# RapideUSB.net
KiCad netlist of a schematic drawn in EAGLE
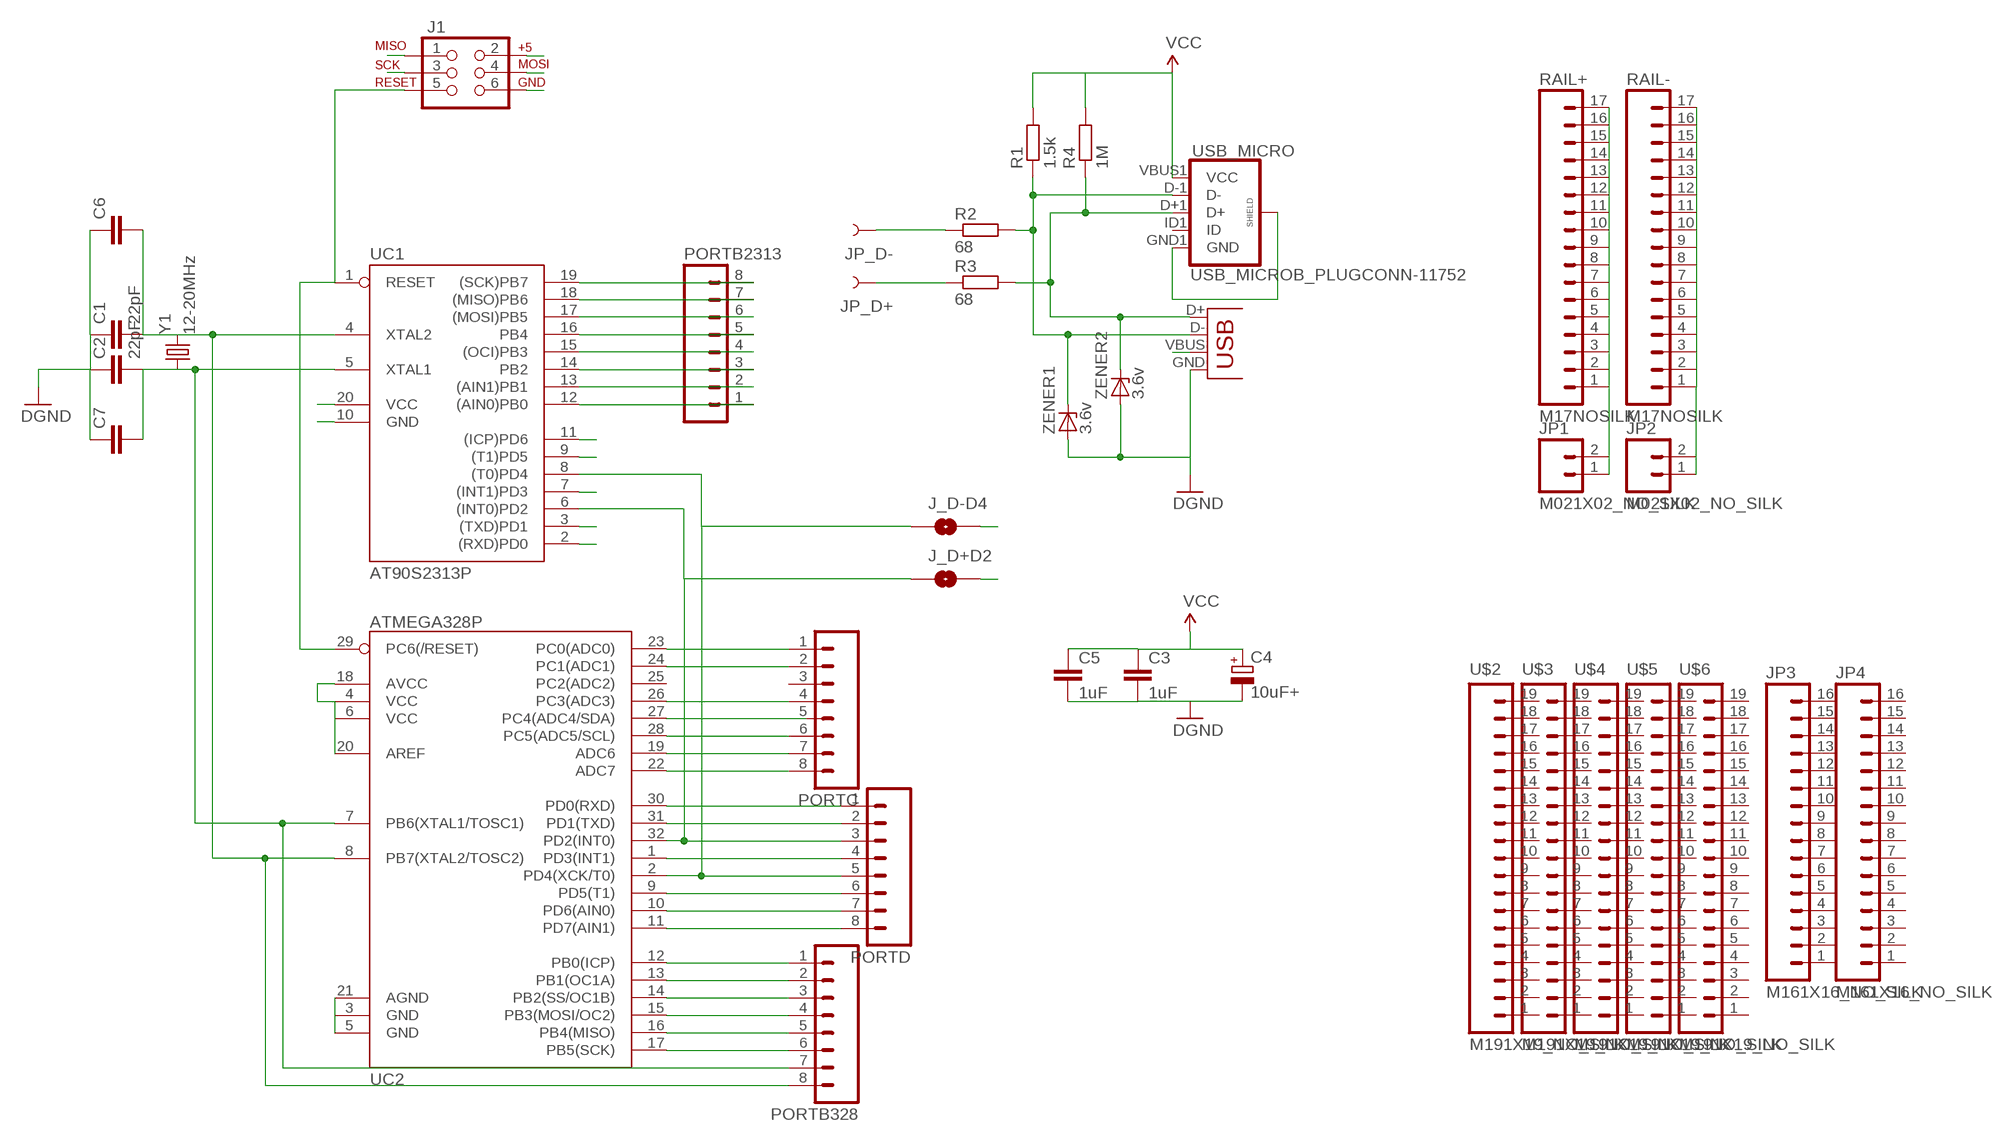
[diagram p0: schematic, sheet 1]

(export (version "E")
  (design (tool "Eeschema 10.0.6"))
  (components
    (comp (ref "C1")
      (value "22pF")
      (footprint "eagle-import:C025-024X044")
      (libsource (lib "eagle-import") (part "C-EU025-024X044"))
    )
    (comp (ref "C2")
      (value "22pF")
      (footprint "eagle-import:C025-024X044")
      (libsource (lib "eagle-import") (part "C-EU025-024X044"))
    )
    (comp (ref "C3")
      (value "1uF")
      (footprint "eagle-import:C025-024X044")
      (libsource (lib "eagle-import") (part "C-EU025-024X044"))
    )
    (comp (ref "C4")
      (value "10uF+")
      (footprint "eagle-import:E2-5")
      (libsource (lib "eagle-import") (part "CPOL-EUE2-5"))
    )
    (comp (ref "C5")
      (value "1uF")
      (footprint "eagle-import:C025-024X044")
      (libsource (lib "eagle-import") (part "C-EU025-024X044"))
    )
    (comp (ref "C6")
      (value "C-EUC1206K")
      (footprint "eagle-import:C1206K")
      (libsource (lib "eagle-import") (part "C-EUC1206K"))
    )
    (comp (ref "C7")
      (value "C-EUC1206K")
      (footprint "eagle-import:C1206K")
      (libsource (lib "eagle-import") (part "C-EUC1206K"))
    )
    (comp (ref "J1")
      (value "AVR_SPI_PRG_6PTH")
      (footprint "eagle-import:2X3")
      (libsource (lib "eagle-import") (part "AVR_SPI_PRG_6PTH"))
    )
    (comp (ref "JP1")
      (value "M021X02_NO_SILK")
      (footprint "eagle-import:1X02_NO_SILK")
      (libsource (lib "eagle-import") (part "M021X02_NO_SILK"))
    )
    (comp (ref "JP2")
      (value "M021X02_NO_SILK")
      (footprint "eagle-import:1X02_NO_SILK")
      (libsource (lib "eagle-import") (part "M021X02_NO_SILK"))
    )
    (comp (ref "JP3")
      (value "M161X16_NO_SILK")
      (footprint "eagle-import:1X16_NO_SILK")
      (libsource (lib "eagle-import") (part "M161X16_NO_SILK"))
    )
    (comp (ref "JP4")
      (value "M161X16_NO_SILK")
      (footprint "eagle-import:1X16_NO_SILK")
      (libsource (lib "eagle-import") (part "M161X16_NO_SILK"))
    )
    (comp (ref "JP_D+")
      (value "TEST-POINT3X5")
      (footprint "eagle-import:PAD.03X.05")
      (libsource (lib "eagle-import") (part "TEST-POINT3X5"))
    )
    (comp (ref "JP_D-")
      (value "TEST-POINT3X5")
      (footprint "eagle-import:PAD.03X.05")
      (libsource (lib "eagle-import") (part "TEST-POINT3X5"))
    )
    (comp (ref "J_D+D2")
      (value "JUMPER-PAD-2-NOYES_SILK")
      (footprint "eagle-import:PAD-JUMPER-2-NO_YES_SILK")
      (libsource (lib "eagle-import") (part "JUMPER-PAD-2-NOYES_SILK"))
    )
    (comp (ref "J_D-D4")
      (value "JUMPER-PAD-2-NOYES_SILK")
      (footprint "eagle-import:PAD-JUMPER-2-NO_YES_SILK")
      (libsource (lib "eagle-import") (part "JUMPER-PAD-2-NOYES_SILK"))
    )
    (comp (ref "PORTB328")
      (value "M081X08")
      (footprint "eagle-import:1X08")
      (libsource (lib "eagle-import") (part "M081X08"))
    )
    (comp (ref "PORTB2313")
      (value "M081X08")
      (footprint "eagle-import:1X08")
      (libsource (lib "eagle-import") (part "M081X08"))
    )
    (comp (ref "PORTC")
      (value "M081X08")
      (footprint "eagle-import:1X08")
      (libsource (lib "eagle-import") (part "M081X08"))
    )
    (comp (ref "PORTD")
      (value "M081X08")
      (footprint "eagle-import:1X08")
      (libsource (lib "eagle-import") (part "M081X08"))
    )
    (comp (ref "R1")
      (value "1.5k")
      (footprint "eagle-import:0204V")
      (libsource (lib "eagle-import") (part "R-EU_0204/2V"))
    )
    (comp (ref "R2")
      (value "68")
      (footprint "eagle-import:0204V")
      (libsource (lib "eagle-import") (part "R-EU_0204/2V"))
    )
    (comp (ref "R3")
      (value "68")
      (footprint "eagle-import:0204V")
      (libsource (lib "eagle-import") (part "R-EU_0204/2V"))
    )
    (comp (ref "R4")
      (value "1M")
      (footprint "eagle-import:0204V")
      (libsource (lib "eagle-import") (part "R-EU_0204/2V"))
    )
    (comp (ref "RAIL+")
      (value "M17NOSILK")
      (footprint "eagle-import:1X17_NO_SILK")
      (libsource (lib "eagle-import") (part "M17NOSILK"))
    )
    (comp (ref "RAIL-")
      (value "M17NOSILK")
      (footprint "eagle-import:1X17_NO_SILK")
      (libsource (lib "eagle-import") (part "M17NOSILK"))
    )
    (comp (ref "U$2")
      (value "M191X19_NO_SILK")
      (footprint "eagle-import:1X19_NO_SILK")
      (libsource (lib "eagle-import") (part "M191X19_NO_SILK"))
    )
    (comp (ref "U$3")
      (value "M191X19_NO_SILK")
      (footprint "eagle-import:1X19_NO_SILK")
      (libsource (lib "eagle-import") (part "M191X19_NO_SILK"))
    )
    (comp (ref "U$4")
      (value "M191X19_NO_SILK")
      (footprint "eagle-import:1X19_NO_SILK")
      (libsource (lib "eagle-import") (part "M191X19_NO_SILK"))
    )
    (comp (ref "U$5")
      (value "M191X19_NO_SILK")
      (footprint "eagle-import:1X19_NO_SILK")
      (libsource (lib "eagle-import") (part "M191X19_NO_SILK"))
    )
    (comp (ref "U$6")
      (value "M191X19_NO_SILK")
      (footprint "eagle-import:1X19_NO_SILK")
      (libsource (lib "eagle-import") (part "M191X19_NO_SILK"))
    )
    (comp (ref "UC1")
      (value "AT90S2313P")
      (footprint "eagle-import:DIL20")
      (libsource (lib "eagle-import") (part "AT90S2313P"))
    )
    (comp (ref "UC2")
      (value "ATMEGA328P")
      (footprint "eagle-import:TQFP32-08")
      (libsource (lib "eagle-import") (part "ATMEGA328_SMT"))
    )
    (comp (ref "USB_MICRO")
      (value "USB_MICROB_PLUGCONN-11752")
      (footprint "eagle-import:USB-B-MICRO-SMD_V03")
      (libsource (lib "eagle-import") (part "USB_MICROB_PLUGCONN-11752"))
    )
    (comp (ref "USB_MINI")
      (value "USBSMD")
      (footprint "eagle-import:USB-MINIB")
      (libsource (lib "eagle-import") (part "USBSMD"))
    )
    (comp (ref "Y1")
      (value "12-20MHz")
      (footprint "eagle-import:HC49U-V")
      (libsource (lib "eagle-import") (part "CRYSTALHC49UV"))
    )
    (comp (ref "ZENER1")
      (value "3.6v")
      (footprint "eagle-import:ZDIO-2.5")
      (libsource (lib "eagle-import") (part "ZENER-DIODEZD-2.5"))
    )
    (comp (ref "ZENER2")
      (value "3.6v")
      (footprint "eagle-import:ZDIO-2.5")
      (libsource (lib "eagle-import") (part "ZENER-DIODEZD-2.5"))
    )
  )
  (nets
    (net (code "1") (name "/D+") (class "Default")
      (node (ref "JP_D+") (pin "P$1") (pinfunction "1_P$1") (pintype "bidirectional"))
      (node (ref "J_D+D2") (pin "2") (pinfunction "2_2") (pintype "passive"))
      (node (ref "R3") (pin "1") (pinfunction "1_1") (pintype "passive"))
    )
    (net (code "2") (name "/D-") (class "Default")
      (node (ref "JP_D-") (pin "P$1") (pinfunction "1_P$1") (pintype "bidirectional"))
      (node (ref "J_D-D4") (pin "2") (pinfunction "2_2") (pintype "passive"))
      (node (ref "R2") (pin "1") (pinfunction "1_1") (pintype "passive"))
    )
    (net (code "3") (name "/D0") (class "Default")
      (node (ref "PORTD") (pin "1") (pinfunction "1_1") (pintype "passive"))
      (node (ref "UC1") (pin "2") (pinfunction "(RXD)PD0_2") (pintype "bidirectional"))
      (node (ref "UC2") (pin "30") (pinfunction "PD0(RXD)_30") (pintype "bidirectional"))
    )
    (net (code "4") (name "/D1") (class "Default")
      (node (ref "PORTD") (pin "2") (pinfunction "2_2") (pintype "passive"))
      (node (ref "UC1") (pin "3") (pinfunction "(TXD)PD1_3") (pintype "bidirectional"))
      (node (ref "UC2") (pin "31") (pinfunction "PD1(TXD)_31") (pintype "bidirectional"))
    )
    (net (code "5") (name "/D3") (class "Default")
      (node (ref "PORTD") (pin "4") (pinfunction "4_4") (pintype "passive"))
      (node (ref "UC1") (pin "7") (pinfunction "(INT1)PD3_7") (pintype "bidirectional"))
      (node (ref "UC2") (pin "1") (pinfunction "PD3(INT1)_1") (pintype "bidirectional"))
    )
    (net (code "6") (name "/D5") (class "Default")
      (node (ref "PORTD") (pin "6") (pinfunction "6_6") (pintype "passive"))
      (node (ref "UC1") (pin "9") (pinfunction "(T1)PD5_9") (pintype "bidirectional"))
      (node (ref "UC2") (pin "9") (pinfunction "PD5(T1)_9") (pintype "bidirectional"))
    )
    (net (code "7") (name "/D6") (class "Default")
      (node (ref "PORTD") (pin "7") (pinfunction "7_7") (pintype "passive"))
      (node (ref "UC1") (pin "11") (pinfunction "(ICP)PD6_11") (pintype "bidirectional"))
      (node (ref "UC2") (pin "10") (pinfunction "PD6(AIN0)_10") (pintype "bidirectional"))
    )
    (net (code "8") (name "/MISO") (class "Default")
      (node (ref "J1") (pin "1") (pinfunction "1_1") (pintype "passive"))
      (node (ref "PORTB2313") (pin "7") (pinfunction "7_7") (pintype "passive"))
      (node (ref "PORTB328") (pin "5") (pinfunction "5_5") (pintype "passive"))
      (node (ref "UC1") (pin "18") (pinfunction "(MISO)PB6_18") (pintype "bidirectional"))
      (node (ref "UC2") (pin "16") (pinfunction "PB4(MISO)_16") (pintype "bidirectional"))
    )
    (net (code "9") (name "/MOSI") (class "Default")
      (node (ref "J1") (pin "4") (pinfunction "4_4") (pintype "passive"))
      (node (ref "PORTB2313") (pin "6") (pinfunction "6_6") (pintype "passive"))
      (node (ref "PORTB328") (pin "4") (pinfunction "4_4") (pintype "passive"))
      (node (ref "UC1") (pin "17") (pinfunction "(MOSI)PB5_17") (pintype "bidirectional"))
      (node (ref "UC2") (pin "15") (pinfunction "PB3(MOSI/OC2)_15") (pintype "bidirectional"))
    )
    (net (code "10") (name "/SCK") (class "Default")
      (node (ref "J1") (pin "3") (pinfunction "3_3") (pintype "passive"))
      (node (ref "PORTB2313") (pin "8") (pinfunction "8_8") (pintype "passive"))
      (node (ref "PORTB328") (pin "6") (pinfunction "6_6") (pintype "passive"))
      (node (ref "UC1") (pin "19") (pinfunction "(SCK)PB7_19") (pintype "bidirectional"))
      (node (ref "UC2") (pin "17") (pinfunction "PB5(SCK)_17") (pintype "bidirectional"))
    )
    (net (code "11") (name "DGND") (class "Default")
      (node (ref "C1") (pin "1") (pinfunction "1_1") (pintype "passive"))
      (node (ref "C2") (pin "1") (pinfunction "1_1") (pintype "passive"))
      (node (ref "C3") (pin "2") (pinfunction "2_2") (pintype "passive"))
      (node (ref "C4") (pin "-") (pinfunction "-_-") (pintype "passive"))
      (node (ref "C5") (pin "2") (pinfunction "2_2") (pintype "passive"))
      (node (ref "C6") (pin "1") (pinfunction "1_1") (pintype "passive"))
      (node (ref "C7") (pin "1") (pinfunction "1_1") (pintype "passive"))
      (node (ref "J1") (pin "6") (pinfunction "6_6") (pintype "passive"))
      (node (ref "JP2") (pin "1") (pinfunction "1_1") (pintype "passive"))
      (node (ref "JP2") (pin "2") (pinfunction "2_2") (pintype "passive"))
      (node (ref "RAIL-") (pin "1") (pinfunction "1_1") (pintype "passive"))
      (node (ref "RAIL-") (pin "10") (pinfunction "10_10") (pintype "passive"))
      (node (ref "RAIL-") (pin "11") (pinfunction "11_11") (pintype "passive"))
      (node (ref "RAIL-") (pin "12") (pinfunction "12_12") (pintype "passive"))
      (node (ref "RAIL-") (pin "13") (pinfunction "13_13") (pintype "passive"))
      (node (ref "RAIL-") (pin "14") (pinfunction "14_14") (pintype "passive"))
      (node (ref "RAIL-") (pin "15") (pinfunction "15_15") (pintype "passive"))
      (node (ref "RAIL-") (pin "16") (pinfunction "16_16") (pintype "passive"))
      (node (ref "RAIL-") (pin "17") (pinfunction "17_17") (pintype "passive"))
      (node (ref "RAIL-") (pin "2") (pinfunction "2_2") (pintype "passive"))
      (node (ref "RAIL-") (pin "3") (pinfunction "3_3") (pintype "passive"))
      (node (ref "RAIL-") (pin "4") (pinfunction "4_4") (pintype "passive"))
      (node (ref "RAIL-") (pin "5") (pinfunction "5_5") (pintype "passive"))
      (node (ref "RAIL-") (pin "6") (pinfunction "6_6") (pintype "passive"))
      (node (ref "RAIL-") (pin "7") (pinfunction "7_7") (pintype "passive"))
      (node (ref "RAIL-") (pin "8") (pinfunction "8_8") (pintype "passive"))
      (node (ref "RAIL-") (pin "9") (pinfunction "9_9") (pintype "passive"))
      (node (ref "UC1") (pin "10") (pinfunction "GND_10") (pintype "power_in"))
      (node (ref "UC2") (pin "21") (pinfunction "AGND_21") (pintype "bidirectional"))
      (node (ref "UC2") (pin "3") (pinfunction "GND_3") (pintype "bidirectional"))
      (node (ref "UC2") (pin "5") (pinfunction "GND_5") (pintype "bidirectional"))
      (node (ref "USB_MICRO") (pin "GND1") (pinfunction "GND_GND1") (pintype "bidirectional"))
      (node (ref "USB_MICRO") (pin "SHIELD1") (pinfunction "SHIELD_SHIELD1") (pintype "bidirectional"))
      (node (ref "USB_MICRO") (pin "SHIELD2") (pinfunction "SHIELD_SHIELD2") (pintype "bidirectional"))
      (node (ref "USB_MICRO") (pin "SHIELD3") (pinfunction "SHIELD_SHIELD3") (pintype "bidirectional"))
      (node (ref "USB_MINI") (pin "GND") (pinfunction "GND_GND") (pintype "bidirectional"))
      (node (ref "ZENER1") (pin "A") (pinfunction "A_A") (pintype "passive"))
      (node (ref "ZENER2") (pin "A") (pinfunction "A_A") (pintype "passive"))
    )
    (net (code "12") (name "Net-(UC1-(AIN0)PB0)") (class "Default")
      (node (ref "PORTB2313") (pin "1") (pinfunction "1_1") (pintype "passive"))
      (node (ref "UC1") (pin "12") (pinfunction "(AIN0)PB0_12") (pintype "bidirectional"))
    )
    (net (code "13") (name "Net-(UC1-(AIN1)PB1)") (class "Default")
      (node (ref "PORTB2313") (pin "2") (pinfunction "2_2") (pintype "passive"))
      (node (ref "UC1") (pin "13") (pinfunction "(AIN1)PB1_13") (pintype "bidirectional"))
    )
    (net (code "14") (name "Net-(UC1-(INT0)PD2)") (class "Default")
      (node (ref "J_D+D2") (pin "1") (pinfunction "1_1") (pintype "passive"))
      (node (ref "PORTD") (pin "3") (pinfunction "3_3") (pintype "passive"))
      (node (ref "UC1") (pin "6") (pinfunction "(INT0)PD2_6") (pintype "bidirectional"))
      (node (ref "UC2") (pin "32") (pinfunction "PD2(INT0)_32") (pintype "bidirectional"))
    )
    (net (code "15") (name "Net-(UC1-(OCI)PB3)") (class "Default")
      (node (ref "PORTB2313") (pin "4") (pinfunction "4_4") (pintype "passive"))
      (node (ref "UC1") (pin "15") (pinfunction "(OCI)PB3_15") (pintype "bidirectional"))
    )
    (net (code "16") (name "Net-(UC1-(T0)PD4)") (class "Default")
      (node (ref "J_D-D4") (pin "1") (pinfunction "1_1") (pintype "passive"))
      (node (ref "PORTD") (pin "5") (pinfunction "5_5") (pintype "passive"))
      (node (ref "UC1") (pin "8") (pinfunction "(T0)PD4_8") (pintype "bidirectional"))
      (node (ref "UC2") (pin "2") (pinfunction "PD4(XCK/T0)_2") (pintype "bidirectional"))
    )
    (net (code "17") (name "Net-(UC1-PB2)") (class "Default")
      (node (ref "PORTB2313") (pin "3") (pinfunction "3_3") (pintype "passive"))
      (node (ref "UC1") (pin "14") (pinfunction "PB2_14") (pintype "bidirectional"))
    )
    (net (code "18") (name "Net-(UC1-PB4)") (class "Default")
      (node (ref "PORTB2313") (pin "5") (pinfunction "5_5") (pintype "passive"))
      (node (ref "UC1") (pin "16") (pinfunction "PB4_16") (pintype "bidirectional"))
    )
    (net (code "19") (name "Net-(UC1-RESET)") (class "Default")
      (node (ref "J1") (pin "5") (pinfunction "5_5") (pintype "passive"))
      (node (ref "UC1") (pin "1") (pinfunction "RESET_1") (pintype "bidirectional"))
      (node (ref "UC2") (pin "29") (pinfunction "PC6(/RESET)_29") (pintype "bidirectional"))
    )
    (net (code "20") (name "Net-(UC1-XTAL1)") (class "Default")
      (node (ref "C2") (pin "2") (pinfunction "2_2") (pintype "passive"))
      (node (ref "C7") (pin "2") (pinfunction "2_2") (pintype "passive"))
      (node (ref "PORTB328") (pin "7") (pinfunction "7_7") (pintype "passive"))
      (node (ref "UC1") (pin "5") (pinfunction "XTAL1_5") (pintype "bidirectional"))
      (node (ref "UC2") (pin "7") (pinfunction "PB6(XTAL1/TOSC1)_7") (pintype "bidirectional"))
      (node (ref "Y1") (pin "1") (pinfunction "1_1") (pintype "passive"))
    )
    (net (code "21") (name "Net-(UC1-XTAL2)") (class "Default")
      (node (ref "C1") (pin "2") (pinfunction "2_2") (pintype "passive"))
      (node (ref "C6") (pin "2") (pinfunction "2_2") (pintype "passive"))
      (node (ref "PORTB328") (pin "8") (pinfunction "8_8") (pintype "passive"))
      (node (ref "UC1") (pin "4") (pinfunction "XTAL2_4") (pintype "bidirectional"))
      (node (ref "UC2") (pin "8") (pinfunction "PB7(XTAL2/TOSC2)_8") (pintype "bidirectional"))
      (node (ref "Y1") (pin "2") (pinfunction "2_2") (pintype "passive"))
    )
    (net (code "22") (name "Net-(UC2-ADC6)") (class "Default")
      (node (ref "PORTC") (pin "7") (pinfunction "7_7") (pintype "passive"))
      (node (ref "UC2") (pin "19") (pinfunction "ADC6_19") (pintype "bidirectional"))
    )
    (net (code "23") (name "Net-(UC2-ADC7)") (class "Default")
      (node (ref "PORTC") (pin "8") (pinfunction "8_8") (pintype "passive"))
      (node (ref "UC2") (pin "22") (pinfunction "ADC7_22") (pintype "bidirectional"))
    )
    (net (code "24") (name "Net-(UC2-PB0(ICP))") (class "Default")
      (node (ref "PORTB328") (pin "1") (pinfunction "1_1") (pintype "passive"))
      (node (ref "UC2") (pin "12") (pinfunction "PB0(ICP)_12") (pintype "bidirectional"))
    )
    (net (code "25") (name "Net-(UC2-PB1(OC1A))") (class "Default")
      (node (ref "PORTB328") (pin "2") (pinfunction "2_2") (pintype "passive"))
      (node (ref "UC2") (pin "13") (pinfunction "PB1(OC1A)_13") (pintype "bidirectional"))
    )
    (net (code "26") (name "Net-(UC2-PB2(SS{slash}OC1B))") (class "Default")
      (node (ref "PORTB328") (pin "3") (pinfunction "3_3") (pintype "passive"))
      (node (ref "UC2") (pin "14") (pinfunction "PB2(SS/OC1B)_14") (pintype "bidirectional"))
    )
    (net (code "27") (name "Net-(UC2-PC0(ADC0))") (class "Default")
      (node (ref "PORTC") (pin "1") (pinfunction "1_1") (pintype "passive"))
      (node (ref "UC2") (pin "23") (pinfunction "PC0(ADC0)_23") (pintype "bidirectional"))
    )
    (net (code "28") (name "Net-(UC2-PC1(ADC1))") (class "Default")
      (node (ref "PORTC") (pin "2") (pinfunction "2_2") (pintype "passive"))
      (node (ref "UC2") (pin "24") (pinfunction "PC1(ADC1)_24") (pintype "bidirectional"))
    )
    (net (code "29") (name "Net-(UC2-PC3(ADC3))") (class "Default")
      (node (ref "PORTC") (pin "4") (pinfunction "4_4") (pintype "passive"))
      (node (ref "UC2") (pin "26") (pinfunction "PC3(ADC3)_26") (pintype "bidirectional"))
    )
    (net (code "30") (name "Net-(UC2-PC4(ADC4{slash}SDA))") (class "Default")
      (node (ref "PORTC") (pin "5") (pinfunction "5_5") (pintype "passive"))
      (node (ref "UC2") (pin "27") (pinfunction "PC4(ADC4/SDA)_27") (pintype "bidirectional"))
    )
    (net (code "31") (name "Net-(UC2-PC5(ADC5{slash}SCL))") (class "Default")
      (node (ref "PORTC") (pin "6") (pinfunction "6_6") (pintype "passive"))
      (node (ref "UC2") (pin "28") (pinfunction "PC5(ADC5/SCL)_28") (pintype "bidirectional"))
    )
    (net (code "32") (name "Net-(UC2-PD7(AIN1))") (class "Default")
      (node (ref "PORTD") (pin "8") (pinfunction "8_8") (pintype "passive"))
      (node (ref "UC2") (pin "11") (pinfunction "PD7(AIN1)_11") (pintype "bidirectional"))
    )
    (net (code "33") (name "Net-(USB_MICRO-D+)") (class "Default")
      (node (ref "R3") (pin "2") (pinfunction "2_2") (pintype "passive"))
      (node (ref "R4") (pin "1") (pinfunction "1_1") (pintype "passive"))
      (node (ref "USB_MICRO") (pin "D+1") (pinfunction "D+_D+1") (pintype "bidirectional"))
      (node (ref "USB_MINI") (pin "D+") (pinfunction "D+_D+") (pintype "bidirectional"))
      (node (ref "ZENER2") (pin "C") (pinfunction "C_C") (pintype "passive"))
    )
    (net (code "34") (name "Net-(USB_MICRO-D-)") (class "Default")
      (node (ref "R1") (pin "1") (pinfunction "1_1") (pintype "passive"))
      (node (ref "R2") (pin "2") (pinfunction "2_2") (pintype "passive"))
      (node (ref "USB_MICRO") (pin "D-1") (pinfunction "D-_D-1") (pintype "bidirectional"))
      (node (ref "USB_MINI") (pin "D-") (pinfunction "D-_D-") (pintype "bidirectional"))
      (node (ref "ZENER1") (pin "C") (pinfunction "C_C") (pintype "passive"))
    )
    (net (code "35") (name "VCC") (class "Default")
      (node (ref "C3") (pin "1") (pinfunction "1_1") (pintype "passive"))
      (node (ref "C4") (pin "+") (pinfunction "+_+") (pintype "passive"))
      (node (ref "C5") (pin "1") (pinfunction "1_1") (pintype "passive"))
      (node (ref "J1") (pin "2") (pinfunction "2_2") (pintype "passive"))
      (node (ref "JP1") (pin "1") (pinfunction "1_1") (pintype "passive"))
      (node (ref "JP1") (pin "2") (pinfunction "2_2") (pintype "passive"))
      (node (ref "R1") (pin "2") (pinfunction "2_2") (pintype "passive"))
      (node (ref "R4") (pin "2") (pinfunction "2_2") (pintype "passive"))
      (node (ref "RAIL+") (pin "1") (pinfunction "1_1") (pintype "passive"))
      (node (ref "RAIL+") (pin "10") (pinfunction "10_10") (pintype "passive"))
      (node (ref "RAIL+") (pin "11") (pinfunction "11_11") (pintype "passive"))
      (node (ref "RAIL+") (pin "12") (pinfunction "12_12") (pintype "passive"))
      (node (ref "RAIL+") (pin "13") (pinfunction "13_13") (pintype "passive"))
      (node (ref "RAIL+") (pin "14") (pinfunction "14_14") (pintype "passive"))
      (node (ref "RAIL+") (pin "15") (pinfunction "15_15") (pintype "passive"))
      (node (ref "RAIL+") (pin "16") (pinfunction "16_16") (pintype "passive"))
      (node (ref "RAIL+") (pin "17") (pinfunction "17_17") (pintype "passive"))
      (node (ref "RAIL+") (pin "2") (pinfunction "2_2") (pintype "passive"))
      (node (ref "RAIL+") (pin "3") (pinfunction "3_3") (pintype "passive"))
      (node (ref "RAIL+") (pin "4") (pinfunction "4_4") (pintype "passive"))
      (node (ref "RAIL+") (pin "5") (pinfunction "5_5") (pintype "passive"))
      (node (ref "RAIL+") (pin "6") (pinfunction "6_6") (pintype "passive"))
      (node (ref "RAIL+") (pin "7") (pinfunction "7_7") (pintype "passive"))
      (node (ref "RAIL+") (pin "8") (pinfunction "8_8") (pintype "passive"))
      (node (ref "RAIL+") (pin "9") (pinfunction "9_9") (pintype "passive"))
      (node (ref "UC1") (pin "20") (pinfunction "VCC_20") (pintype "power_in"))
      (node (ref "UC2") (pin "18") (pinfunction "AVCC_18") (pintype "bidirectional"))
      (node (ref "UC2") (pin "20") (pinfunction "AREF_20") (pintype "bidirectional"))
      (node (ref "UC2") (pin "4") (pinfunction "VCC_4") (pintype "bidirectional"))
      (node (ref "UC2") (pin "6") (pinfunction "VCC_6") (pintype "bidirectional"))
      (node (ref "USB_MICRO") (pin "VBUS1") (pinfunction "VCC_VBUS1") (pintype "bidirectional"))
      (node (ref "USB_MINI") (pin "VBUS") (pinfunction "VBUS_VBUS") (pintype "bidirectional"))
    )
    (net (code "36") (name "unconnected-(JP3-Pad1)") (class "Default")
      (node (ref "JP3") (pin "1") (pinfunction "1_1") (pintype "passive"))
    )
    (net (code "37") (name "unconnected-(JP3-Pad2)") (class "Default")
      (node (ref "JP3") (pin "2") (pinfunction "2_2") (pintype "passive"))
    )
    (net (code "38") (name "unconnected-(JP3-Pad3)") (class "Default")
      (node (ref "JP3") (pin "3") (pinfunction "3_3") (pintype "passive"))
    )
    (net (code "39") (name "unconnected-(JP3-Pad4)") (class "Default")
      (node (ref "JP3") (pin "4") (pinfunction "4_4") (pintype "passive"))
    )
    (net (code "40") (name "unconnected-(JP3-Pad5)") (class "Default")
      (node (ref "JP3") (pin "5") (pinfunction "5_5") (pintype "passive"))
    )
    (net (code "41") (name "unconnected-(JP3-Pad6)") (class "Default")
      (node (ref "JP3") (pin "6") (pinfunction "6_6") (pintype "passive"))
    )
    (net (code "42") (name "unconnected-(JP3-Pad7)") (class "Default")
      (node (ref "JP3") (pin "7") (pinfunction "7_7") (pintype "passive"))
    )
    (net (code "43") (name "unconnected-(JP3-Pad8)") (class "Default")
      (node (ref "JP3") (pin "8") (pinfunction "8_8") (pintype "passive"))
    )
    (net (code "44") (name "unconnected-(JP3-Pad9)") (class "Default")
      (node (ref "JP3") (pin "9") (pinfunction "9_9") (pintype "passive"))
    )
    (net (code "45") (name "unconnected-(JP3-Pad10)") (class "Default")
      (node (ref "JP3") (pin "10") (pinfunction "10_10") (pintype "passive"))
    )
    (net (code "46") (name "unconnected-(JP3-Pad11)") (class "Default")
      (node (ref "JP3") (pin "11") (pinfunction "11_11") (pintype "passive"))
    )
    (net (code "47") (name "unconnected-(JP3-Pad12)") (class "Default")
      (node (ref "JP3") (pin "12") (pinfunction "12_12") (pintype "passive"))
    )
    (net (code "48") (name "unconnected-(JP3-Pad13)") (class "Default")
      (node (ref "JP3") (pin "13") (pinfunction "13_13") (pintype "passive"))
    )
    (net (code "49") (name "unconnected-(JP3-Pad14)") (class "Default")
      (node (ref "JP3") (pin "14") (pinfunction "14_14") (pintype "passive"))
    )
    (net (code "50") (name "unconnected-(JP3-Pad15)") (class "Default")
      (node (ref "JP3") (pin "15") (pinfunction "15_15") (pintype "passive"))
    )
    (net (code "51") (name "unconnected-(JP3-Pad16)") (class "Default")
      (node (ref "JP3") (pin "16") (pinfunction "16_16") (pintype "passive"))
    )
    (net (code "52") (name "unconnected-(JP4-Pad1)") (class "Default")
      (node (ref "JP4") (pin "1") (pinfunction "1_1") (pintype "passive"))
    )
    (net (code "53") (name "unconnected-(JP4-Pad2)") (class "Default")
      (node (ref "JP4") (pin "2") (pinfunction "2_2") (pintype "passive"))
    )
    (net (code "54") (name "unconnected-(JP4-Pad3)") (class "Default")
      (node (ref "JP4") (pin "3") (pinfunction "3_3") (pintype "passive"))
    )
    (net (code "55") (name "unconnected-(JP4-Pad4)") (class "Default")
      (node (ref "JP4") (pin "4") (pinfunction "4_4") (pintype "passive"))
    )
    (net (code "56") (name "unconnected-(JP4-Pad5)") (class "Default")
      (node (ref "JP4") (pin "5") (pinfunction "5_5") (pintype "passive"))
    )
    (net (code "57") (name "unconnected-(JP4-Pad6)") (class "Default")
      (node (ref "JP4") (pin "6") (pinfunction "6_6") (pintype "passive"))
    )
    (net (code "58") (name "unconnected-(JP4-Pad7)") (class "Default")
      (node (ref "JP4") (pin "7") (pinfunction "7_7") (pintype "passive"))
    )
    (net (code "59") (name "unconnected-(JP4-Pad8)") (class "Default")
      (node (ref "JP4") (pin "8") (pinfunction "8_8") (pintype "passive"))
    )
    (net (code "60") (name "unconnected-(JP4-Pad9)") (class "Default")
      (node (ref "JP4") (pin "9") (pinfunction "9_9") (pintype "passive"))
    )
    (net (code "61") (name "unconnected-(JP4-Pad10)") (class "Default")
      (node (ref "JP4") (pin "10") (pinfunction "10_10") (pintype "passive"))
    )
    (net (code "62") (name "unconnected-(JP4-Pad11)") (class "Default")
      (node (ref "JP4") (pin "11") (pinfunction "11_11") (pintype "passive"))
    )
    (net (code "63") (name "unconnected-(JP4-Pad12)") (class "Default")
      (node (ref "JP4") (pin "12") (pinfunction "12_12") (pintype "passive"))
    )
    (net (code "64") (name "unconnected-(JP4-Pad13)") (class "Default")
      (node (ref "JP4") (pin "13") (pinfunction "13_13") (pintype "passive"))
    )
    (net (code "65") (name "unconnected-(JP4-Pad14)") (class "Default")
      (node (ref "JP4") (pin "14") (pinfunction "14_14") (pintype "passive"))
    )
    (net (code "66") (name "unconnected-(JP4-Pad15)") (class "Default")
      (node (ref "JP4") (pin "15") (pinfunction "15_15") (pintype "passive"))
    )
    (net (code "67") (name "unconnected-(JP4-Pad16)") (class "Default")
      (node (ref "JP4") (pin "16") (pinfunction "16_16") (pintype "passive"))
    )
    (net (code "68") (name "unconnected-(PORTC-Pad3)") (class "Default")
      (node (ref "PORTC") (pin "3") (pinfunction "3_3") (pintype "passive"))
    )
    (net (code "69") (name "unconnected-(U$2-Pad1)") (class "Default")
      (node (ref "U$2") (pin "1") (pinfunction "1_1") (pintype "passive"))
    )
    (net (code "70") (name "unconnected-(U$2-Pad2)") (class "Default")
      (node (ref "U$2") (pin "2") (pinfunction "2_2") (pintype "passive"))
    )
    (net (code "71") (name "unconnected-(U$2-Pad3)") (class "Default")
      (node (ref "U$2") (pin "3") (pinfunction "3_3") (pintype "passive"))
    )
    (net (code "72") (name "unconnected-(U$2-Pad4)") (class "Default")
      (node (ref "U$2") (pin "4") (pinfunction "4_4") (pintype "passive"))
    )
    (net (code "73") (name "unconnected-(U$2-Pad5)") (class "Default")
      (node (ref "U$2") (pin "5") (pinfunction "5_5") (pintype "passive"))
    )
    (net (code "74") (name "unconnected-(U$2-Pad6)") (class "Default")
      (node (ref "U$2") (pin "6") (pinfunction "6_6") (pintype "passive"))
    )
    (net (code "75") (name "unconnected-(U$2-Pad7)") (class "Default")
      (node (ref "U$2") (pin "7") (pinfunction "7_7") (pintype "passive"))
    )
    (net (code "76") (name "unconnected-(U$2-Pad8)") (class "Default")
      (node (ref "U$2") (pin "8") (pinfunction "8_8") (pintype "passive"))
    )
    (net (code "77") (name "unconnected-(U$2-Pad9)") (class "Default")
      (node (ref "U$2") (pin "9") (pinfunction "9_9") (pintype "passive"))
    )
    (net (code "78") (name "unconnected-(U$2-Pad10)") (class "Default")
      (node (ref "U$2") (pin "10") (pinfunction "10_10") (pintype "passive"))
    )
    (net (code "79") (name "unconnected-(U$2-Pad11)") (class "Default")
      (node (ref "U$2") (pin "11") (pinfunction "11_11") (pintype "passive"))
    )
    (net (code "80") (name "unconnected-(U$2-Pad12)") (class "Default")
      (node (ref "U$2") (pin "12") (pinfunction "12_12") (pintype "passive"))
    )
    (net (code "81") (name "unconnected-(U$2-Pad13)") (class "Default")
      (node (ref "U$2") (pin "13") (pinfunction "13_13") (pintype "passive"))
    )
    (net (code "82") (name "unconnected-(U$2-Pad14)") (class "Default")
      (node (ref "U$2") (pin "14") (pinfunction "14_14") (pintype "passive"))
    )
    (net (code "83") (name "unconnected-(U$2-Pad15)") (class "Default")
      (node (ref "U$2") (pin "15") (pinfunction "15_15") (pintype "passive"))
    )
    (net (code "84") (name "unconnected-(U$2-Pad16)") (class "Default")
      (node (ref "U$2") (pin "16") (pinfunction "16_16") (pintype "passive"))
    )
    (net (code "85") (name "unconnected-(U$2-Pad17)") (class "Default")
      (node (ref "U$2") (pin "17") (pinfunction "17_17") (pintype "passive"))
    )
    (net (code "86") (name "unconnected-(U$2-Pad18)") (class "Default")
      (node (ref "U$2") (pin "18") (pinfunction "18_18") (pintype "passive"))
    )
    (net (code "87") (name "unconnected-(U$2-Pad19)") (class "Default")
      (node (ref "U$2") (pin "19") (pinfunction "19_19") (pintype "passive"))
    )
    (net (code "88") (name "unconnected-(U$3-Pad1)") (class "Default")
      (node (ref "U$3") (pin "1") (pinfunction "1_1") (pintype "passive"))
    )
    (net (code "89") (name "unconnected-(U$3-Pad2)") (class "Default")
      (node (ref "U$3") (pin "2") (pinfunction "2_2") (pintype "passive"))
    )
    (net (code "90") (name "unconnected-(U$3-Pad3)") (class "Default")
      (node (ref "U$3") (pin "3") (pinfunction "3_3") (pintype "passive"))
    )
    (net (code "91") (name "unconnected-(U$3-Pad4)") (class "Default")
      (node (ref "U$3") (pin "4") (pinfunction "4_4") (pintype "passive"))
    )
    (net (code "92") (name "unconnected-(U$3-Pad5)") (class "Default")
      (node (ref "U$3") (pin "5") (pinfunction "5_5") (pintype "passive"))
    )
    (net (code "93") (name "unconnected-(U$3-Pad6)") (class "Default")
      (node (ref "U$3") (pin "6") (pinfunction "6_6") (pintype "passive"))
    )
    (net (code "94") (name "unconnected-(U$3-Pad7)") (class "Default")
      (node (ref "U$3") (pin "7") (pinfunction "7_7") (pintype "passive"))
    )
    (net (code "95") (name "unconnected-(U$3-Pad8)") (class "Default")
      (node (ref "U$3") (pin "8") (pinfunction "8_8") (pintype "passive"))
    )
    (net (code "96") (name "unconnected-(U$3-Pad9)") (class "Default")
      (node (ref "U$3") (pin "9") (pinfunction "9_9") (pintype "passive"))
    )
    (net (code "97") (name "unconnected-(U$3-Pad10)") (class "Default")
      (node (ref "U$3") (pin "10") (pinfunction "10_10") (pintype "passive"))
    )
    (net (code "98") (name "unconnected-(U$3-Pad11)") (class "Default")
      (node (ref "U$3") (pin "11") (pinfunction "11_11") (pintype "passive"))
    )
    (net (code "99") (name "unconnected-(U$3-Pad12)") (class "Default")
      (node (ref "U$3") (pin "12") (pinfunction "12_12") (pintype "passive"))
    )
    (net (code "100") (name "unconnected-(U$3-Pad13)") (class "Default")
      (node (ref "U$3") (pin "13") (pinfunction "13_13") (pintype "passive"))
    )
    (net (code "101") (name "unconnected-(U$3-Pad14)") (class "Default")
      (node (ref "U$3") (pin "14") (pinfunction "14_14") (pintype "passive"))
    )
    (net (code "102") (name "unconnected-(U$3-Pad15)") (class "Default")
      (node (ref "U$3") (pin "15") (pinfunction "15_15") (pintype "passive"))
    )
    (net (code "103") (name "unconnected-(U$3-Pad16)") (class "Default")
      (node (ref "U$3") (pin "16") (pinfunction "16_16") (pintype "passive"))
    )
    (net (code "104") (name "unconnected-(U$3-Pad17)") (class "Default")
      (node (ref "U$3") (pin "17") (pinfunction "17_17") (pintype "passive"))
    )
    (net (code "105") (name "unconnected-(U$3-Pad18)") (class "Default")
      (node (ref "U$3") (pin "18") (pinfunction "18_18") (pintype "passive"))
    )
    (net (code "106") (name "unconnected-(U$3-Pad19)") (class "Default")
      (node (ref "U$3") (pin "19") (pinfunction "19_19") (pintype "passive"))
    )
    (net (code "107") (name "unconnected-(U$4-Pad1)") (class "Default")
      (node (ref "U$4") (pin "1") (pinfunction "1_1") (pintype "passive"))
    )
    (net (code "108") (name "unconnected-(U$4-Pad2)") (class "Default")
      (node (ref "U$4") (pin "2") (pinfunction "2_2") (pintype "passive"))
    )
    (net (code "109") (name "unconnected-(U$4-Pad3)") (class "Default")
      (node (ref "U$4") (pin "3") (pinfunction "3_3") (pintype "passive"))
    )
    (net (code "110") (name "unconnected-(U$4-Pad4)") (class "Default")
      (node (ref "U$4") (pin "4") (pinfunction "4_4") (pintype "passive"))
    )
    (net (code "111") (name "unconnected-(U$4-Pad5)") (class "Default")
      (node (ref "U$4") (pin "5") (pinfunction "5_5") (pintype "passive"))
    )
    (net (code "112") (name "unconnected-(U$4-Pad6)") (class "Default")
      (node (ref "U$4") (pin "6") (pinfunction "6_6") (pintype "passive"))
    )
    (net (code "113") (name "unconnected-(U$4-Pad7)") (class "Default")
      (node (ref "U$4") (pin "7") (pinfunction "7_7") (pintype "passive"))
    )
    (net (code "114") (name "unconnected-(U$4-Pad8)") (class "Default")
      (node (ref "U$4") (pin "8") (pinfunction "8_8") (pintype "passive"))
    )
    (net (code "115") (name "unconnected-(U$4-Pad9)") (class "Default")
      (node (ref "U$4") (pin "9") (pinfunction "9_9") (pintype "passive"))
    )
    (net (code "116") (name "unconnected-(U$4-Pad10)") (class "Default")
      (node (ref "U$4") (pin "10") (pinfunction "10_10") (pintype "passive"))
    )
    (net (code "117") (name "unconnected-(U$4-Pad11)") (class "Default")
      (node (ref "U$4") (pin "11") (pinfunction "11_11") (pintype "passive"))
    )
    (net (code "118") (name "unconnected-(U$4-Pad12)") (class "Default")
      (node (ref "U$4") (pin "12") (pinfunction "12_12") (pintype "passive"))
    )
    (net (code "119") (name "unconnected-(U$4-Pad13)") (class "Default")
      (node (ref "U$4") (pin "13") (pinfunction "13_13") (pintype "passive"))
    )
    (net (code "120") (name "unconnected-(U$4-Pad14)") (class "Default")
      (node (ref "U$4") (pin "14") (pinfunction "14_14") (pintype "passive"))
    )
    (net (code "121") (name "unconnected-(U$4-Pad15)") (class "Default")
      (node (ref "U$4") (pin "15") (pinfunction "15_15") (pintype "passive"))
    )
    (net (code "122") (name "unconnected-(U$4-Pad16)") (class "Default")
      (node (ref "U$4") (pin "16") (pinfunction "16_16") (pintype "passive"))
    )
    (net (code "123") (name "unconnected-(U$4-Pad17)") (class "Default")
      (node (ref "U$4") (pin "17") (pinfunction "17_17") (pintype "passive"))
    )
    (net (code "124") (name "unconnected-(U$4-Pad18)") (class "Default")
      (node (ref "U$4") (pin "18") (pinfunction "18_18") (pintype "passive"))
    )
    (net (code "125") (name "unconnected-(U$4-Pad19)") (class "Default")
      (node (ref "U$4") (pin "19") (pinfunction "19_19") (pintype "passive"))
    )
    (net (code "126") (name "unconnected-(U$5-Pad1)") (class "Default")
      (node (ref "U$5") (pin "1") (pinfunction "1_1") (pintype "passive"))
    )
    (net (code "127") (name "unconnected-(U$5-Pad2)") (class "Default")
      (node (ref "U$5") (pin "2") (pinfunction "2_2") (pintype "passive"))
    )
    (net (code "128") (name "unconnected-(U$5-Pad3)") (class "Default")
      (node (ref "U$5") (pin "3") (pinfunction "3_3") (pintype "passive"))
    )
    (net (code "129") (name "unconnected-(U$5-Pad4)") (class "Default")
      (node (ref "U$5") (pin "4") (pinfunction "4_4") (pintype "passive"))
    )
    (net (code "130") (name "unconnected-(U$5-Pad5)") (class "Default")
      (node (ref "U$5") (pin "5") (pinfunction "5_5") (pintype "passive"))
    )
    (net (code "131") (name "unconnected-(U$5-Pad6)") (class "Default")
      (node (ref "U$5") (pin "6") (pinfunction "6_6") (pintype "passive"))
    )
    (net (code "132") (name "unconnected-(U$5-Pad7)") (class "Default")
      (node (ref "U$5") (pin "7") (pinfunction "7_7") (pintype "passive"))
    )
    (net (code "133") (name "unconnected-(U$5-Pad8)") (class "Default")
      (node (ref "U$5") (pin "8") (pinfunction "8_8") (pintype "passive"))
    )
    (net (code "134") (name "unconnected-(U$5-Pad9)") (class "Default")
      (node (ref "U$5") (pin "9") (pinfunction "9_9") (pintype "passive"))
    )
    (net (code "135") (name "unconnected-(U$5-Pad10)") (class "Default")
      (node (ref "U$5") (pin "10") (pinfunction "10_10") (pintype "passive"))
    )
    (net (code "136") (name "unconnected-(U$5-Pad11)") (class "Default")
      (node (ref "U$5") (pin "11") (pinfunction "11_11") (pintype "passive"))
    )
    (net (code "137") (name "unconnected-(U$5-Pad12)") (class "Default")
      (node (ref "U$5") (pin "12") (pinfunction "12_12") (pintype "passive"))
    )
    (net (code "138") (name "unconnected-(U$5-Pad13)") (class "Default")
      (node (ref "U$5") (pin "13") (pinfunction "13_13") (pintype "passive"))
    )
    (net (code "139") (name "unconnected-(U$5-Pad14)") (class "Default")
      (node (ref "U$5") (pin "14") (pinfunction "14_14") (pintype "passive"))
    )
    (net (code "140") (name "unconnected-(U$5-Pad15)") (class "Default")
      (node (ref "U$5") (pin "15") (pinfunction "15_15") (pintype "passive"))
    )
    (net (code "141") (name "unconnected-(U$5-Pad16)") (class "Default")
      (node (ref "U$5") (pin "16") (pinfunction "16_16") (pintype "passive"))
    )
    (net (code "142") (name "unconnected-(U$5-Pad17)") (class "Default")
      (node (ref "U$5") (pin "17") (pinfunction "17_17") (pintype "passive"))
    )
    (net (code "143") (name "unconnected-(U$5-Pad18)") (class "Default")
      (node (ref "U$5") (pin "18") (pinfunction "18_18") (pintype "passive"))
    )
    (net (code "144") (name "unconnected-(U$5-Pad19)") (class "Default")
      (node (ref "U$5") (pin "19") (pinfunction "19_19") (pintype "passive"))
    )
    (net (code "145") (name "unconnected-(U$6-Pad1)") (class "Default")
      (node (ref "U$6") (pin "1") (pinfunction "1_1") (pintype "passive"))
    )
    (net (code "146") (name "unconnected-(U$6-Pad2)") (class "Default")
      (node (ref "U$6") (pin "2") (pinfunction "2_2") (pintype "passive"))
    )
    (net (code "147") (name "unconnected-(U$6-Pad3)") (class "Default")
      (node (ref "U$6") (pin "3") (pinfunction "3_3") (pintype "passive"))
    )
    (net (code "148") (name "unconnected-(U$6-Pad4)") (class "Default")
      (node (ref "U$6") (pin "4") (pinfunction "4_4") (pintype "passive"))
    )
    (net (code "149") (name "unconnected-(U$6-Pad5)") (class "Default")
      (node (ref "U$6") (pin "5") (pinfunction "5_5") (pintype "passive"))
    )
    (net (code "150") (name "unconnected-(U$6-Pad6)") (class "Default")
      (node (ref "U$6") (pin "6") (pinfunction "6_6") (pintype "passive"))
    )
    (net (code "151") (name "unconnected-(U$6-Pad7)") (class "Default")
      (node (ref "U$6") (pin "7") (pinfunction "7_7") (pintype "passive"))
    )
    (net (code "152") (name "unconnected-(U$6-Pad8)") (class "Default")
      (node (ref "U$6") (pin "8") (pinfunction "8_8") (pintype "passive"))
    )
    (net (code "153") (name "unconnected-(U$6-Pad9)") (class "Default")
      (node (ref "U$6") (pin "9") (pinfunction "9_9") (pintype "passive"))
    )
    (net (code "154") (name "unconnected-(U$6-Pad10)") (class "Default")
      (node (ref "U$6") (pin "10") (pinfunction "10_10") (pintype "passive"))
    )
    (net (code "155") (name "unconnected-(U$6-Pad11)") (class "Default")
      (node (ref "U$6") (pin "11") (pinfunction "11_11") (pintype "passive"))
    )
    (net (code "156") (name "unconnected-(U$6-Pad12)") (class "Default")
      (node (ref "U$6") (pin "12") (pinfunction "12_12") (pintype "passive"))
    )
    (net (code "157") (name "unconnected-(U$6-Pad13)") (class "Default")
      (node (ref "U$6") (pin "13") (pinfunction "13_13") (pintype "passive"))
    )
    (net (code "158") (name "unconnected-(U$6-Pad14)") (class "Default")
      (node (ref "U$6") (pin "14") (pinfunction "14_14") (pintype "passive"))
    )
    (net (code "159") (name "unconnected-(U$6-Pad15)") (class "Default")
      (node (ref "U$6") (pin "15") (pinfunction "15_15") (pintype "passive"))
    )
    (net (code "160") (name "unconnected-(U$6-Pad16)") (class "Default")
      (node (ref "U$6") (pin "16") (pinfunction "16_16") (pintype "passive"))
    )
    (net (code "161") (name "unconnected-(U$6-Pad17)") (class "Default")
      (node (ref "U$6") (pin "17") (pinfunction "17_17") (pintype "passive"))
    )
    (net (code "162") (name "unconnected-(U$6-Pad18)") (class "Default")
      (node (ref "U$6") (pin "18") (pinfunction "18_18") (pintype "passive"))
    )
    (net (code "163") (name "unconnected-(U$6-Pad19)") (class "Default")
      (node (ref "U$6") (pin "19") (pinfunction "19_19") (pintype "passive"))
    )
    (net (code "164") (name "unconnected-(UC2-PC2(ADC2)-Pad25)") (class "Default")
      (node (ref "UC2") (pin "25") (pinfunction "PC2(ADC2)_25") (pintype "bidirectional"))
    )
    (net (code "165") (name "unconnected-(USB_MICRO-ID-PadID1)") (class "Default")
      (node (ref "USB_MICRO") (pin "ID1") (pinfunction "ID_ID1") (pintype "bidirectional"))
    )
  )
)
